# Keg_Cop_-_RJ45_-_6-Pack.net
KiCad netlist of a schematic drawn in EAGLE
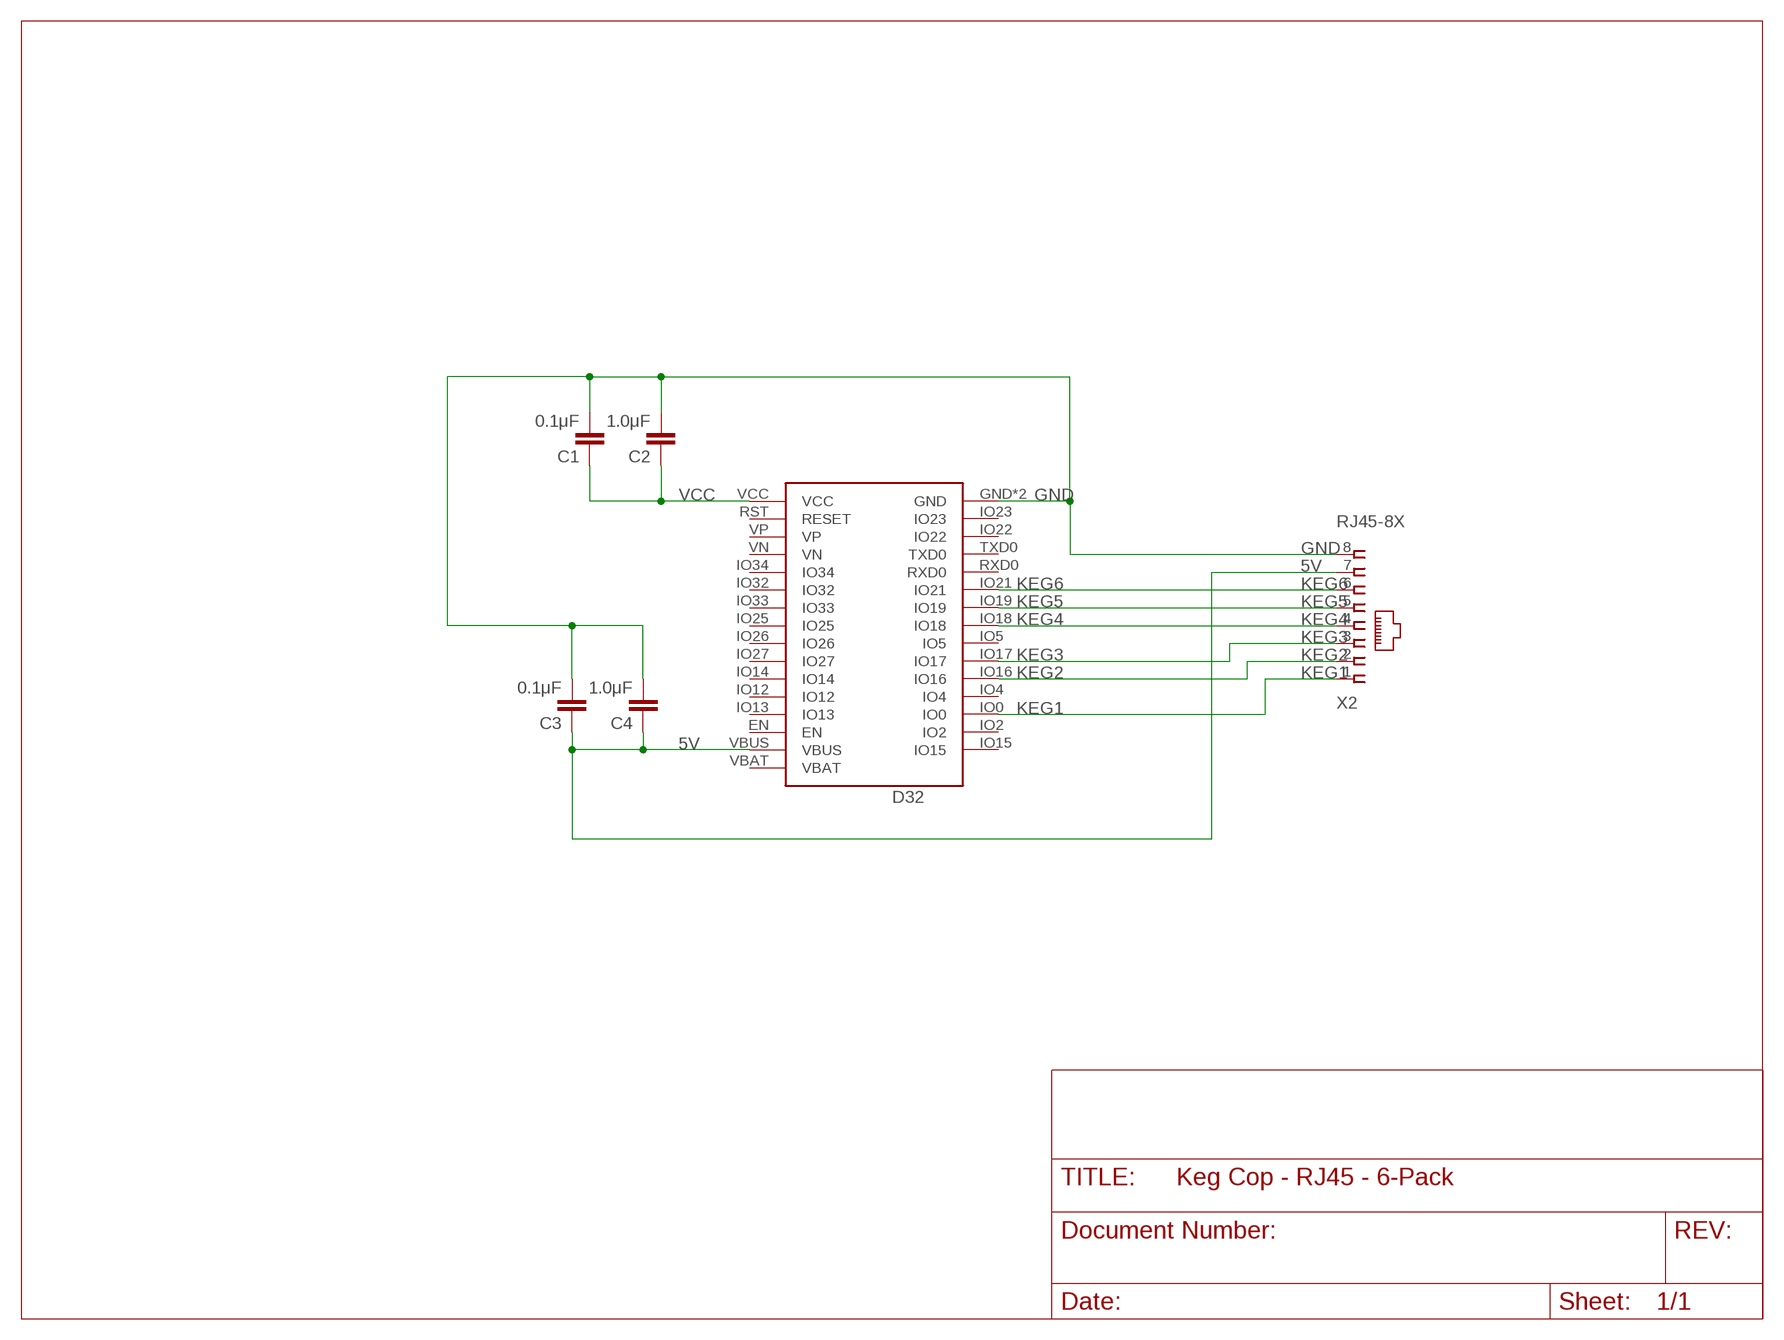
[diagram p0: schematic, sheet 1]

(export (version "E")
  (design (tool "Eeschema 10.0.6"))
  (components
    (comp (ref "C1")
      (value "0.1μF")
      (footprint "eagle-import:CAP_PTH-2.54")
      (libsource (lib "eagle-import") (part "CAP_CERAMIC_2.54"))
    )
    (comp (ref "C2")
      (value "1.0μF")
      (footprint "eagle-import:CAP_PTH-2.54")
      (libsource (lib "eagle-import") (part "CAP_CERAMIC_2.54"))
    )
    (comp (ref "C3")
      (value "0.1μF")
      (footprint "eagle-import:CAP_PTH-2.54")
      (libsource (lib "eagle-import") (part "CAP_CERAMIC_2.54"))
    )
    (comp (ref "C4")
      (value "1.0μF")
      (footprint "eagle-import:CAP_PTH-2.54")
      (libsource (lib "eagle-import") (part "CAP_CERAMIC_2.54"))
    )
    (comp (ref "D32")
      (value "Lolin D32")
      (footprint "eagle-import:D32_NO_BATT")
      (libsource (lib "eagle-import") (part "WEMOS-D32D32_NO_BATT"))
    )
    (comp (ref "X2")
      (value "RJ45-8X")
      (footprint "eagle-import:RJ45-NO-SHIELD")
      (libsource (lib "eagle-import") (part "RJ45-8X"))
    )
  )
  (nets
    (net (code "1") (name "/5V") (class "Default")
      (node (ref "C3") (pin "1") (pinfunction "1_1") (pintype "passive"))
      (node (ref "C4") (pin "1") (pinfunction "1_1") (pintype "passive"))
      (node (ref "D32") (pin "VBUS") (pinfunction "VBUS_VBUS") (pintype "bidirectional"))
      (node (ref "X2") (pin "7") (pinfunction "7_7") (pintype "passive"))
    )
    (net (code "2") (name "/GND") (class "Default")
      (node (ref "C1") (pin "2") (pinfunction "2_2") (pintype "passive"))
      (node (ref "C2") (pin "2") (pinfunction "2_2") (pintype "passive"))
      (node (ref "C3") (pin "2") (pinfunction "2_2") (pintype "passive"))
      (node (ref "C4") (pin "2") (pinfunction "2_2") (pintype "passive"))
      (node (ref "D32") (pin "GND") (pinfunction "GND_GND") (pintype "power_in"))
      (node (ref "D32") (pin "GND2") (pinfunction "GND_GND2") (pintype "power_in"))
      (node (ref "X2") (pin "8") (pinfunction "8_8") (pintype "passive"))
    )
    (net (code "3") (name "/KEG1") (class "Default")
      (node (ref "D32") (pin "IO0") (pinfunction "IO0_IO0") (pintype "bidirectional"))
      (node (ref "X2") (pin "1") (pinfunction "1_1") (pintype "passive"))
    )
    (net (code "4") (name "/KEG2") (class "Default")
      (node (ref "D32") (pin "IO16") (pinfunction "IO16_IO16") (pintype "bidirectional"))
      (node (ref "X2") (pin "2") (pinfunction "2_2") (pintype "passive"))
    )
    (net (code "5") (name "/KEG3") (class "Default")
      (node (ref "D32") (pin "IO17") (pinfunction "IO17_IO17") (pintype "bidirectional"))
      (node (ref "X2") (pin "3") (pinfunction "3_3") (pintype "passive"))
    )
    (net (code "6") (name "/KEG4") (class "Default")
      (node (ref "D32") (pin "IO18") (pinfunction "IO18_IO18") (pintype "bidirectional"))
      (node (ref "X2") (pin "4") (pinfunction "4_4") (pintype "passive"))
    )
    (net (code "7") (name "/KEG5") (class "Default")
      (node (ref "D32") (pin "IO19") (pinfunction "IO19_IO19") (pintype "bidirectional"))
      (node (ref "X2") (pin "5") (pinfunction "5_5") (pintype "passive"))
    )
    (net (code "8") (name "/KEG6") (class "Default")
      (node (ref "D32") (pin "IO21") (pinfunction "IO21_IO21") (pintype "bidirectional"))
      (node (ref "X2") (pin "6") (pinfunction "6_6") (pintype "passive"))
    )
    (net (code "9") (name "/VCC") (class "Default")
      (node (ref "C1") (pin "1") (pinfunction "1_1") (pintype "passive"))
      (node (ref "C2") (pin "1") (pinfunction "1_1") (pintype "passive"))
      (node (ref "D32") (pin "VCC") (pinfunction "VCC_VCC") (pintype "power_in"))
    )
    (net (code "10") (name "unconnected-(D32-PadEN)") (class "Default")
      (node (ref "D32") (pin "EN") (pinfunction "EN_EN") (pintype "bidirectional"))
    )
    (net (code "11") (name "unconnected-(D32-PadIO2)") (class "Default")
      (node (ref "D32") (pin "IO2") (pinfunction "IO2_IO2") (pintype "bidirectional"))
    )
    (net (code "12") (name "unconnected-(D32-PadIO4)") (class "Default")
      (node (ref "D32") (pin "IO4") (pinfunction "IO4_IO4") (pintype "bidirectional"))
    )
    (net (code "13") (name "unconnected-(D32-PadIO5)") (class "Default")
      (node (ref "D32") (pin "IO5") (pinfunction "IO5_IO5") (pintype "bidirectional"))
    )
    (net (code "14") (name "unconnected-(D32-PadIO12)") (class "Default")
      (node (ref "D32") (pin "IO12") (pinfunction "IO12_IO12") (pintype "bidirectional"))
    )
    (net (code "15") (name "unconnected-(D32-PadIO13)") (class "Default")
      (node (ref "D32") (pin "IO13") (pinfunction "IO13_IO13") (pintype "bidirectional"))
    )
    (net (code "16") (name "unconnected-(D32-PadIO14)") (class "Default")
      (node (ref "D32") (pin "IO14") (pinfunction "IO14_IO14") (pintype "bidirectional"))
    )
    (net (code "17") (name "unconnected-(D32-PadIO15)") (class "Default")
      (node (ref "D32") (pin "IO15") (pinfunction "IO15_IO15") (pintype "bidirectional"))
    )
    (net (code "18") (name "unconnected-(D32-PadIO22)") (class "Default")
      (node (ref "D32") (pin "IO22") (pinfunction "IO22_IO22") (pintype "bidirectional"))
    )
    (net (code "19") (name "unconnected-(D32-PadIO23)") (class "Default")
      (node (ref "D32") (pin "IO23") (pinfunction "IO23_IO23") (pintype "bidirectional"))
    )
    (net (code "20") (name "unconnected-(D32-PadIO25)") (class "Default")
      (node (ref "D32") (pin "IO25") (pinfunction "IO25_IO25") (pintype "bidirectional"))
    )
    (net (code "21") (name "unconnected-(D32-PadIO26)") (class "Default")
      (node (ref "D32") (pin "IO26") (pinfunction "IO26_IO26") (pintype "bidirectional"))
    )
    (net (code "22") (name "unconnected-(D32-PadIO27)") (class "Default")
      (node (ref "D32") (pin "IO27") (pinfunction "IO27_IO27") (pintype "bidirectional"))
    )
    (net (code "23") (name "unconnected-(D32-PadIO32)") (class "Default")
      (node (ref "D32") (pin "IO32") (pinfunction "IO32_IO32") (pintype "bidirectional"))
    )
    (net (code "24") (name "unconnected-(D32-PadIO33)") (class "Default")
      (node (ref "D32") (pin "IO33") (pinfunction "IO33_IO33") (pintype "bidirectional"))
    )
    (net (code "25") (name "unconnected-(D32-PadIO34)") (class "Default")
      (node (ref "D32") (pin "IO34") (pinfunction "IO34_IO34") (pintype "bidirectional"))
    )
    (net (code "26") (name "unconnected-(D32-PadRXD0)") (class "Default")
      (node (ref "D32") (pin "RXD0") (pinfunction "RXD0_RXD0") (pintype "input"))
    )
    (net (code "27") (name "unconnected-(D32-PadTXD0)") (class "Default")
      (node (ref "D32") (pin "TXD0") (pinfunction "TXD0_TXD0") (pintype "output"))
    )
    (net (code "28") (name "unconnected-(D32-PadVBAT)") (class "Default")
      (node (ref "D32") (pin "VBAT") (pinfunction "VBAT_VBAT") (pintype "bidirectional"))
    )
    (net (code "29") (name "unconnected-(D32-PadVN)") (class "Default")
      (node (ref "D32") (pin "VN") (pinfunction "VN_VN") (pintype "bidirectional"))
    )
    (net (code "30") (name "unconnected-(D32-PadVP)") (class "Default")
      (node (ref "D32") (pin "VP") (pinfunction "VP_VP") (pintype "bidirectional"))
    )
    (net (code "31") (name "unconnected-(D32-RESET-PadRST)") (class "Default")
      (node (ref "D32") (pin "RST") (pinfunction "RESET_RST") (pintype "bidirectional"))
    )
  )
)
